# WaterInfo.net
KiCad netlist of a schematic drawn in EasyEDA Pro
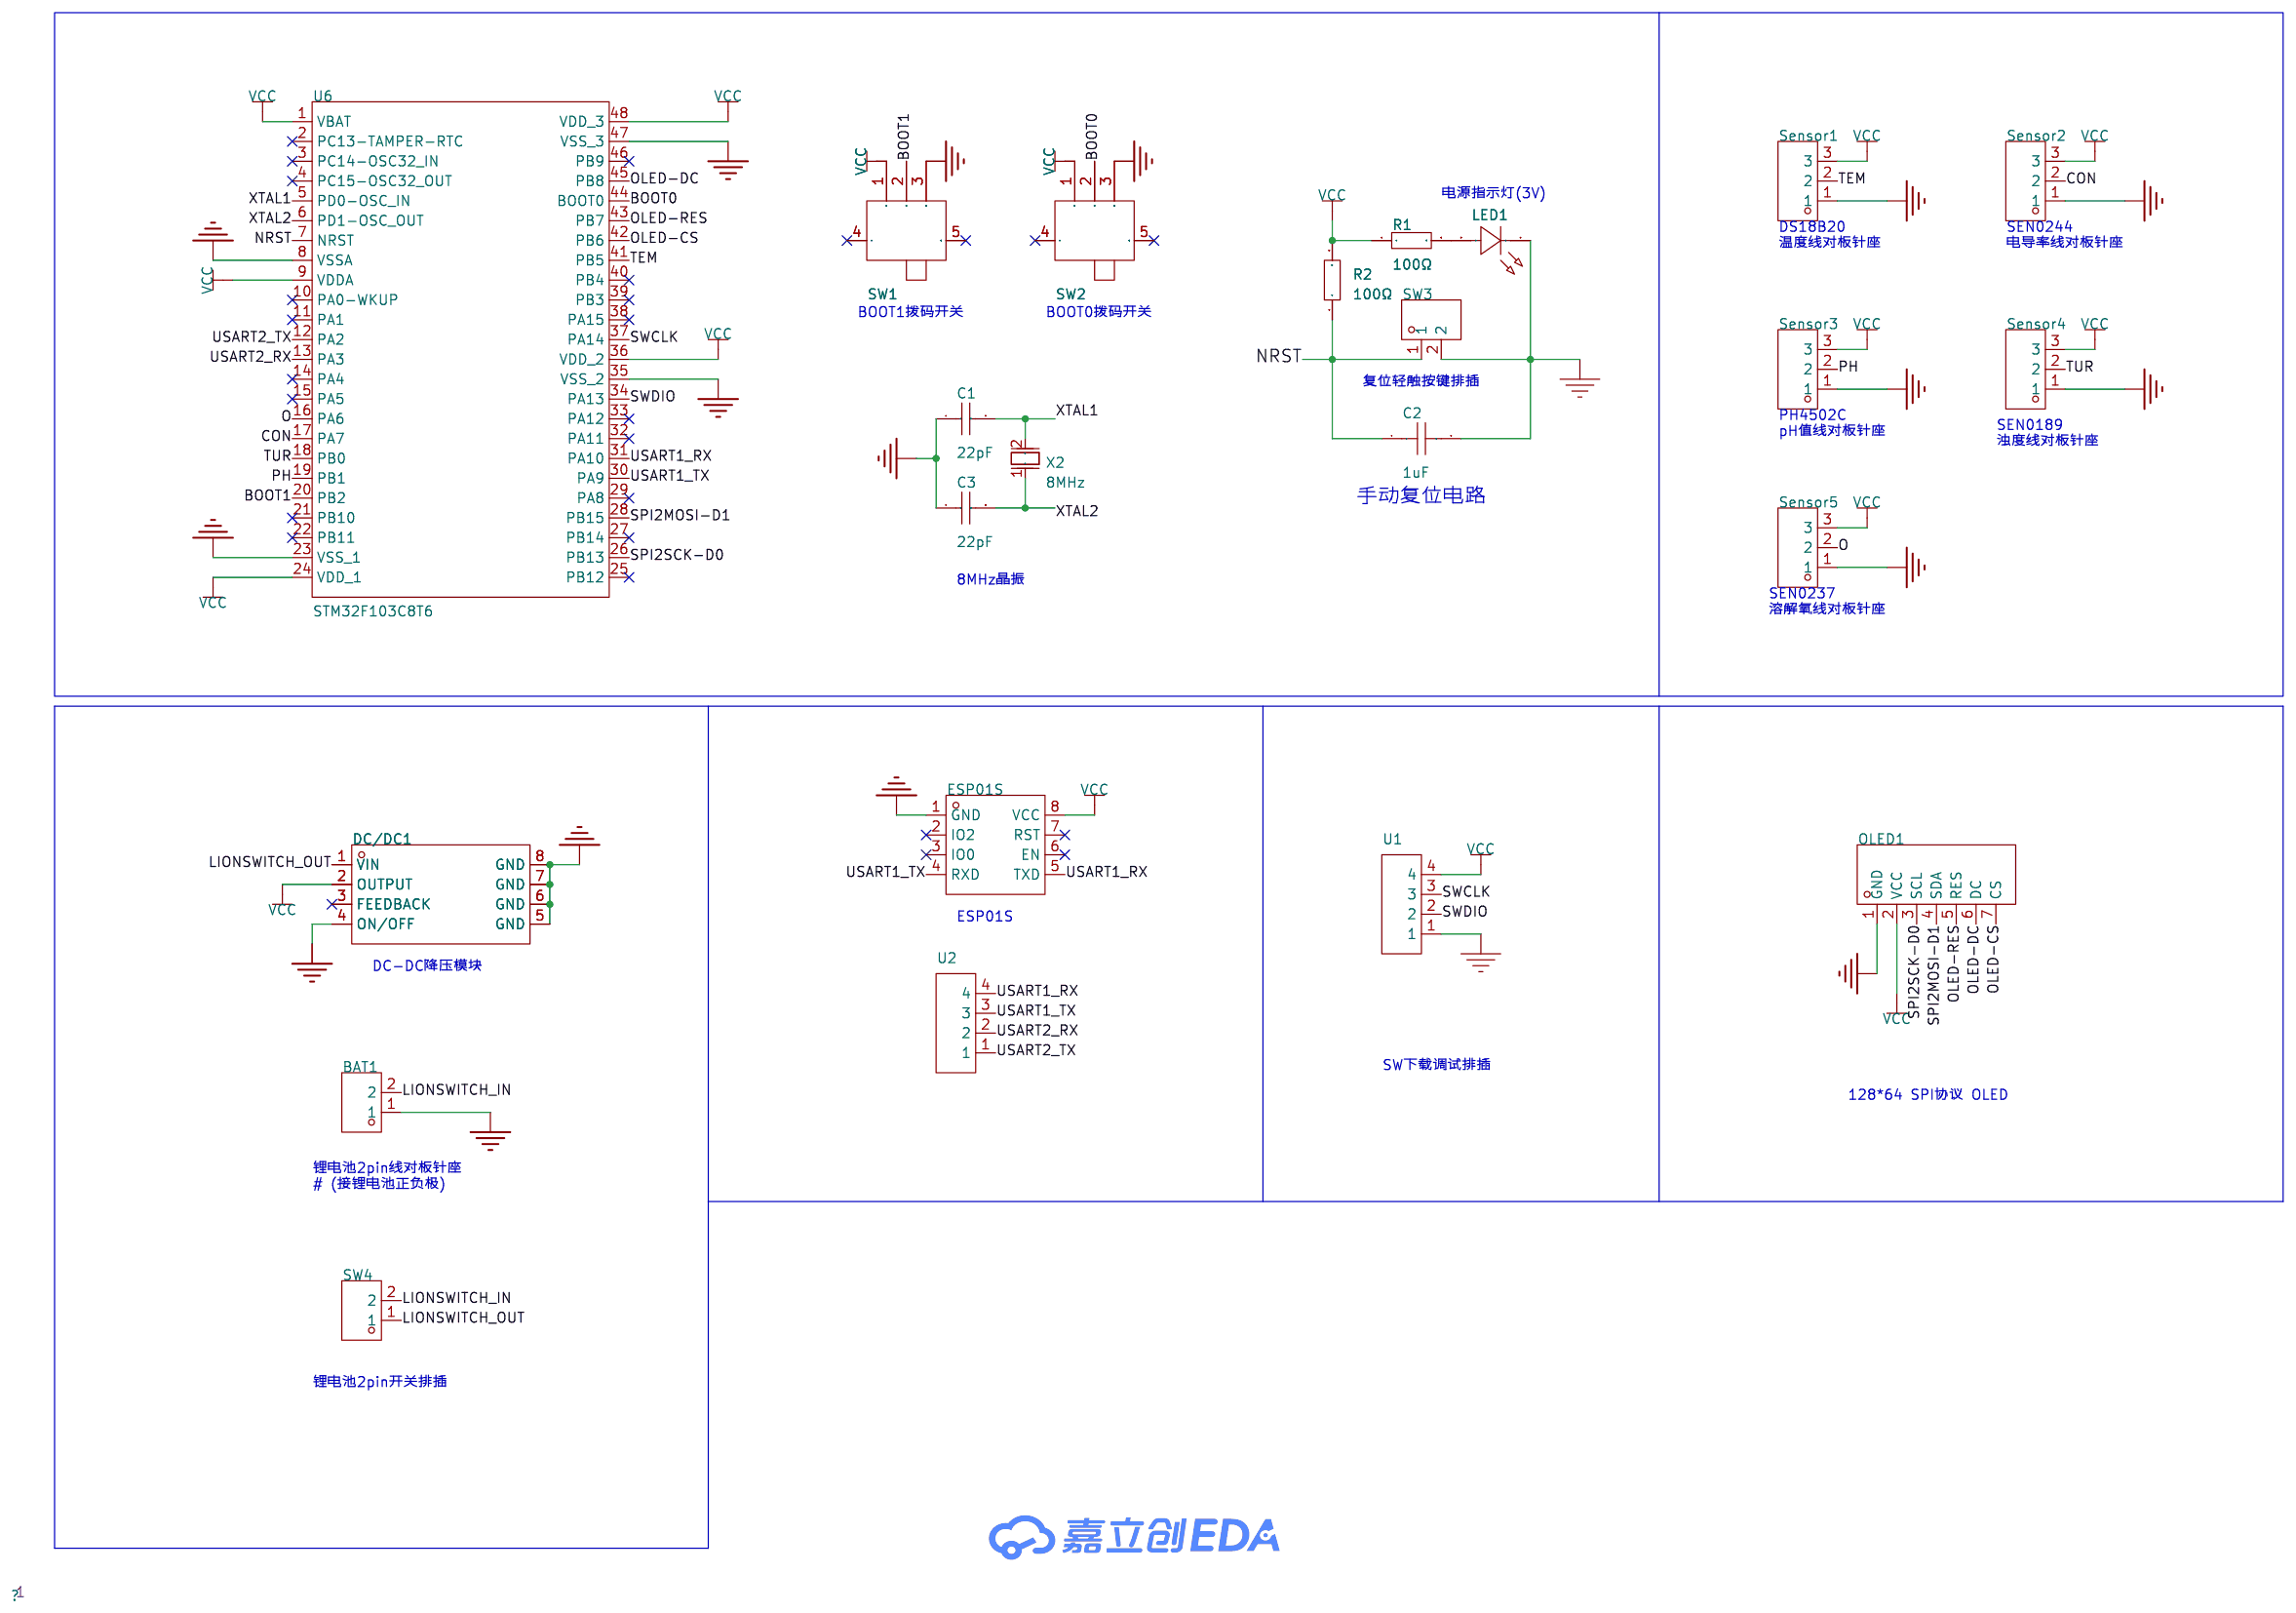
[diagram p0: schematic sheet]

(export (version "E")
  (design (tool "Eeschema 10.0.6"))
  (components
    (comp (ref "BAT1")
      (value "WAFER-PH2.0-2PZZ")
      (footprint "easyedapro:CONN-TH_2P-P2.00_HC-PH-2A-M")
      (fields (field (name "Manufacturer") "XUNPU(讯普)"))
      (libsource (lib "easyedapro") (part "WAFER-PH2.0-2PZZ"))
    )
    (comp (ref "C1")
      (value "22pF")
      (footprint "easyedapro:C0603")
      (description "容值:22pF;精度:±5%;额定电压:50V;材质(温度系数):C0G;")
      (fields
        (field (name "Manufacturer Part") "CL10C220JB8NNNC")
        (field (name "Manufacturer") "SAMSUNG(三星)")
      )
      (libsource (lib "easyedapro") (part "CL10C220JB8NNNC"))
    )
    (comp (ref "C2")
      (value "1uF")
      (footprint "easyedapro:C0603")
      (description "容值:1uF;精度:±10%;额定电压:50V;材质(温度系数):X5R;")
      (fields
        (field (name "Manufacturer Part") "CL10A105KB8NNNC")
        (field (name "Manufacturer") "SAMSUNG(三星)")
      )
      (libsource (lib "easyedapro") (part "CL10A105KB8NNNC"))
    )
    (comp (ref "C3")
      (value "22pF")
      (footprint "easyedapro:C0603")
      (description "容值:22pF;精度:±5%;额定电压:50V;材质(温度系数):C0G;")
      (fields
        (field (name "Manufacturer Part") "CL10C220JB8NNNC")
        (field (name "Manufacturer") "SAMSUNG(三星)")
      )
      (libsource (lib "easyedapro") (part "CL10C220JB8NNNC"))
    )
    (comp (ref "DC/DC1")
      (value "XL1509-3.3")
      (footprint "easyedapro:SOIC-8_L4.9-W3.9-P1.27-LS6.0-BL")
      (description "功能类型:降压型;输出类型:固定;工作电压:4.5V~40V;输出电压:3.3V;输出电流:2A;")
      (fields (field (name "Manufacturer") "UMW(友台半导体)"))
      (libsource (lib "easyedapro") (part "XL1509-3.3"))
    )
    (comp (ref "ESP01S")
      (value "2.4GHz")
      (footprint "easyedapro:WIFIM-TH_8P-L24.7-W14.4-P2.54")
      (description "核心处理器:ESP8266芯片;频率:2.4GHz;天线形式:板载PCB天线;发射功率:16dBm;接收灵敏度:-90dBm;")
      (fields (field (name "Manufacturer Part") "ESP-01S") (field (name "Manufacturer") "Ai-Thinker(安信可)"))
      (libsource (lib "easyedapro") (part "ESP-01S_C503582"))
    )
    (comp (ref "LED1")
      (value "XL-502UGD")
      (footprint "easyedapro:LED-TH_BD5.9-P2.54-RD_GREEN")
      (fields (field (name "Manufacturer") "XINGLIGHT(成兴光)"))
      (libsource (lib "easyedapro") (part "XL-502UGD"))
    )
    (comp (ref "OLED1")
      (value "HS96L01W4S03")
      (footprint "easyedapro:OLED-TH_HS96L01W4S03")
      (fields (field (name "Manufacturer") "HS(汉昇)"))
      (libsource (lib "easyedapro") (part "HS96L01W4S03"))
    )
    (comp (ref "R1")
      (value "100Ω")
      (footprint "easyedapro:R0805")
      (description "电阻类型:薄膜电阻;阻值:100Ω;精度:±0.1%;功率:125mW;最大工作电压:150V;温度系数:±25ppm/°C;")
      (fields (field (name "Manufacturer Part") "RT0805BRD07100RL") (field (name "Manufacturer") "YAGEO(国巨)"))
      (libsource (lib "easyedapro") (part "RT0805BRD07100RL"))
    )
    (comp (ref "R2")
      (value "100Ω")
      (footprint "easyedapro:R0805")
      (description "电阻类型:薄膜电阻;阻值:100Ω;精度:±0.1%;功率:125mW;最大工作电压:150V;温度系数:±25ppm/°C;")
      (fields (field (name "Manufacturer Part") "RT0805BRD07100RL") (field (name "Manufacturer") "YAGEO(国巨)"))
      (libsource (lib "easyedapro") (part "RT0805BRD07100RL"))
    )
    (comp (ref "Sensor1")
      (value "2.54-1*3P")
      (footprint "easyedapro:CONN-TH_C722693")
      (description "插针结构:1x3P;间距:2.5mm;安装方式:直插;参考系列:-;总PIN数:3P;排数:1;每排PIN数:3;行距:-;额定电流:2A;工作温度范围:-25°C~+85°C;")
      (fields (field (name "Manufacturer") "CAX(创都)"))
      (libsource (lib "easyedapro") (part "2.54-1*3P"))
    )
    (comp (ref "Sensor2")
      (value "WAFER-PH2.0-3PZZ")
      (footprint "easyedapro:CONN-TH_PH2.0D-L-3P")
      (fields (field (name "Manufacturer") "XUNPU(讯普)"))
      (libsource (lib "easyedapro") (part "WAFER-PH2.0-3PZZ"))
    )
    (comp (ref "Sensor3")
      (value "2.54-1*3P")
      (footprint "easyedapro:CONN-TH_C722693")
      (description "插针结构:1x3P;间距:2.5mm;安装方式:直插;参考系列:-;总PIN数:3P;排数:1;每排PIN数:3;行距:-;额定电流:2A;工作温度范围:-25°C~+85°C;")
      (fields (field (name "Manufacturer") "CAX(创都)"))
      (libsource (lib "easyedapro") (part "2.54-1*3P"))
    )
    (comp (ref "Sensor4")
      (value "WAFER-PH2.0-3PZZ")
      (footprint "easyedapro:CONN-TH_PH2.0D-L-3P")
      (fields (field (name "Manufacturer") "XUNPU(讯普)"))
      (libsource (lib "easyedapro") (part "WAFER-PH2.0-3PZZ"))
    )
    (comp (ref "Sensor5")
      (value "2.54-1*3P")
      (footprint "easyedapro:CONN-TH_C722693")
      (description "插针结构:1x3P;间距:2.5mm;安装方式:直插;参考系列:-;总PIN数:3P;排数:1;每排PIN数:3;行距:-;额定电流:2A;工作温度范围:-25°C~+85°C;")
      (fields (field (name "Manufacturer") "CAX(创都)"))
      (libsource (lib "easyedapro") (part "2.54-1*3P"))
    )
    (comp (ref "SW1")
      (value "MINI MSK12CO2")
      (footprint "easyedapro:SW-SMD_MSK12CO2")
      (description "电路结构:单刀双掷;安装方式:卧贴;开关颜色:-;额定电流(DC):50mA;额定电压(DC):12V;额定电流(AC):-;额定电压(AC):-;机械寿命:1万次;")
      (fields (field (name "Manufacturer") "SHOU HAN(首韩)"))
      (libsource (lib "easyedapro") (part "MINI MSK12CO2"))
    )
    (comp (ref "SW2")
      (value "MINI MSK12CO2")
      (footprint "easyedapro:SW-SMD_MSK12CO2")
      (description "电路结构:单刀双掷;安装方式:卧贴;开关颜色:-;额定电流(DC):50mA;额定电压(DC):12V;额定电流(AC):-;额定电压(AC):-;机械寿命:1万次;")
      (fields (field (name "Manufacturer") "SHOU HAN(首韩)"))
      (libsource (lib "easyedapro") (part "MINI MSK12CO2"))
    )
    (comp (ref "SW3")
      (value "WAFER-PH2.0-2PZZ")
      (footprint "easyedapro:CONN-TH_2P-P2.00_HC-PH-2A-M")
      (fields (field (name "Manufacturer") "XUNPU(讯普)"))
      (libsource (lib "easyedapro") (part "WAFER-PH2.0-2PZZ"))
    )
    (comp (ref "SW4")
      (value "WAFER-PH2.0-2PZZ")
      (footprint "easyedapro:CONN-TH_2P-P2.00_HC-PH-2A-M")
      (fields (field (name "Manufacturer") "XUNPU(讯普)"))
      (libsource (lib "easyedapro") (part "WAFER-PH2.0-2PZZ"))
    )
    (comp (ref "U1")
      (value "HX PZ2.54-1x4P ZZ")
      (footprint "easyedapro:HDR-TH_4P-P2.54-V-M")
      (fields (field (name "Manufacturer") "hanxia(韩下)"))
      (libsource (lib "easyedapro") (part "HX PZ2.54-1X4P ZZ"))
    )
    (comp (ref "U2")
      (value "HX PZ2.54-1x4P ZZ")
      (footprint "easyedapro:HDR-TH_4P-P2.54-V-M")
      (fields (field (name "Manufacturer") "hanxia(韩下)"))
      (libsource (lib "easyedapro") (part "HX PZ2.54-1X4P ZZ"))
    )
    (comp (ref "U6")
      (value "STM32F103C8T6")
      (footprint "easyedapro:LQFP-48_L7.0-W7.0-P0.50-LS9.0-BL")
      (description "CPU内核:ARM-M3;CPU最大主频:72MHz;应用领域:-;")
      (fields (field (name "Manufacturer") "ST(意法半导体)"))
      (libsource (lib "easyedapro") (part "STM32F103C8T6"))
    )
    (comp (ref "X2")
      (value "8MHz")
      (footprint "easyedapro:OSC-SMD_2P-L3.2-W2.5")
      (description "晶振类型:贴片晶振;频率:8MHz;常温频差:±30ppm;负载电容:12pF;")
      (fields (field (name "Manufacturer Part") "A308000003") (field (name "Manufacturer") "TXC(晶技)"))
      (libsource (lib "easyedapro") (part "A308000003"))
    )
  )
  (nets
    (net (code "1") (name "/BOOT0") (class "Default")
      (node (ref "SW2") (pin "2") (pinfunction "2_2") (pintype "unspecified"))
      (node (ref "U6") (pin "44") (pinfunction "BOOT0_44") (pintype "unspecified"))
    )
    (net (code "2") (name "/BOOT1") (class "Default")
      (node (ref "SW1") (pin "2") (pinfunction "2_2") (pintype "unspecified"))
      (node (ref "U6") (pin "20") (pinfunction "PB2_20") (pintype "unspecified"))
    )
    (net (code "3") (name "/CON") (class "Default")
      (node (ref "Sensor2") (pin "2") (pinfunction "2_2") (pintype "unspecified"))
      (node (ref "U6") (pin "17") (pinfunction "PA7_17") (pintype "unspecified"))
    )
    (net (code "4") (name "/LIONSWITCH_IN") (class "Default")
      (node (ref "BAT1") (pin "2") (pinfunction "2_2") (pintype "unspecified"))
      (node (ref "SW4") (pin "2") (pinfunction "2_2") (pintype "unspecified"))
    )
    (net (code "5") (name "/LIONSWITCH_OUT") (class "Default")
      (node (ref "DC/DC1") (pin "1") (pinfunction "VIN_1") (pintype "unspecified"))
      (node (ref "SW4") (pin "1") (pinfunction "1_1") (pintype "unspecified"))
    )
    (net (code "6") (name "/NRST") (class "Default")
      (node (ref "C2") (pin "1") (pinfunction "1_1") (pintype "unspecified"))
      (node (ref "R2") (pin "1") (pinfunction "1_1") (pintype "input"))
      (node (ref "SW3") (pin "1") (pinfunction "1_1") (pintype "unspecified"))
      (node (ref "U6") (pin "7") (pinfunction "NRST_7") (pintype "unspecified"))
    )
    (net (code "7") (name "/O") (class "Default")
      (node (ref "Sensor5") (pin "2") (pinfunction "2_2") (pintype "unspecified"))
      (node (ref "U6") (pin "16") (pinfunction "PA6_16") (pintype "unspecified"))
    )
    (net (code "8") (name "/OLED-CS") (class "Default")
      (node (ref "OLED1") (pin "7") (pinfunction "CS_7") (pintype "unspecified"))
      (node (ref "U6") (pin "42") (pinfunction "PB6_42") (pintype "unspecified"))
    )
    (net (code "9") (name "/OLED-DC") (class "Default")
      (node (ref "OLED1") (pin "6") (pinfunction "DC_6") (pintype "unspecified"))
      (node (ref "U6") (pin "45") (pinfunction "PB8_45") (pintype "unspecified"))
    )
    (net (code "10") (name "/OLED-RES") (class "Default")
      (node (ref "OLED1") (pin "5") (pinfunction "RES_5") (pintype "unspecified"))
      (node (ref "U6") (pin "43") (pinfunction "PB7_43") (pintype "unspecified"))
    )
    (net (code "11") (name "/PH") (class "Default")
      (node (ref "Sensor3") (pin "2") (pinfunction "2_2") (pintype "unspecified"))
      (node (ref "U6") (pin "19") (pinfunction "PB1_19") (pintype "unspecified"))
    )
    (net (code "12") (name "/SPI2MOSI-D1") (class "Default")
      (node (ref "OLED1") (pin "4") (pinfunction "SDA_4") (pintype "unspecified"))
      (node (ref "U6") (pin "28") (pinfunction "PB15_28") (pintype "unspecified"))
    )
    (net (code "13") (name "/SPI2SCK-D0") (class "Default")
      (node (ref "OLED1") (pin "3") (pinfunction "SCL_3") (pintype "unspecified"))
      (node (ref "U6") (pin "26") (pinfunction "PB13_26") (pintype "unspecified"))
    )
    (net (code "14") (name "/SWCLK") (class "Default")
      (node (ref "U1") (pin "3") (pinfunction "3_3") (pintype "unspecified"))
      (node (ref "U6") (pin "37") (pinfunction "PA14_37") (pintype "unspecified"))
    )
    (net (code "15") (name "/SWDIO") (class "Default")
      (node (ref "U1") (pin "2") (pinfunction "2_2") (pintype "unspecified"))
      (node (ref "U6") (pin "34") (pinfunction "PA13_34") (pintype "unspecified"))
    )
    (net (code "16") (name "/TEM") (class "Default")
      (node (ref "Sensor1") (pin "2") (pinfunction "2_2") (pintype "unspecified"))
      (node (ref "U6") (pin "41") (pinfunction "PB5_41") (pintype "unspecified"))
    )
    (net (code "17") (name "/TUR") (class "Default")
      (node (ref "Sensor4") (pin "2") (pinfunction "2_2") (pintype "unspecified"))
      (node (ref "U6") (pin "18") (pinfunction "PB0_18") (pintype "unspecified"))
    )
    (net (code "18") (name "/USART1_RX") (class "Default")
      (node (ref "ESP01S") (pin "5") (pinfunction "TXD_5") (pintype "unspecified"))
      (node (ref "U2") (pin "4") (pinfunction "4_4") (pintype "unspecified"))
      (node (ref "U6") (pin "31") (pinfunction "PA10_31") (pintype "unspecified"))
    )
    (net (code "19") (name "/USART1_TX") (class "Default")
      (node (ref "ESP01S") (pin "4") (pinfunction "RXD_4") (pintype "unspecified"))
      (node (ref "U2") (pin "3") (pinfunction "3_3") (pintype "unspecified"))
      (node (ref "U6") (pin "30") (pinfunction "PA9_30") (pintype "unspecified"))
    )
    (net (code "20") (name "/USART2_RX") (class "Default")
      (node (ref "U2") (pin "2") (pinfunction "2_2") (pintype "unspecified"))
      (node (ref "U6") (pin "13") (pinfunction "PA3_13") (pintype "unspecified"))
    )
    (net (code "21") (name "/USART2_TX") (class "Default")
      (node (ref "U2") (pin "1") (pinfunction "1_1") (pintype "unspecified"))
      (node (ref "U6") (pin "12") (pinfunction "PA2_12") (pintype "unspecified"))
    )
    (net (code "22") (name "/XTAL1") (class "Default")
      (node (ref "C1") (pin "2") (pinfunction "2_2") (pintype "input"))
      (node (ref "U6") (pin "5") (pinfunction "PD0-OSC_IN_5") (pintype "unspecified"))
      (node (ref "X2") (pin "2") (pinfunction "2_2") (pintype "unspecified"))
    )
    (net (code "23") (name "/XTAL2") (class "Default")
      (node (ref "C3") (pin "2") (pinfunction "2_2") (pintype "input"))
      (node (ref "U6") (pin "6") (pinfunction "PD1-OSC_OUT_6") (pintype "unspecified"))
      (node (ref "X2") (pin "1") (pinfunction "1_1") (pintype "unspecified"))
    )
    (net (code "24") (name "GND") (class "Default")
      (node (ref "BAT1") (pin "1") (pinfunction "1_1") (pintype "unspecified"))
      (node (ref "C1") (pin "1") (pinfunction "1_1") (pintype "input"))
      (node (ref "C2") (pin "2") (pinfunction "2_2") (pintype "unspecified"))
      (node (ref "C3") (pin "1") (pinfunction "1_1") (pintype "input"))
      (node (ref "DC/DC1") (pin "4") (pinfunction "ON/OFF_4") (pintype "unspecified"))
      (node (ref "DC/DC1") (pin "5") (pinfunction "GND_5") (pintype "unspecified"))
      (node (ref "DC/DC1") (pin "6") (pinfunction "GND_6") (pintype "unspecified"))
      (node (ref "DC/DC1") (pin "7") (pinfunction "GND_7") (pintype "unspecified"))
      (node (ref "DC/DC1") (pin "8") (pinfunction "GND_8") (pintype "unspecified"))
      (node (ref "ESP01S") (pin "1") (pinfunction "GND_1") (pintype "unspecified"))
      (node (ref "LED1") (pin "1") (pinfunction "K_1") (pintype "unspecified"))
      (node (ref "OLED1") (pin "1") (pinfunction "GND_1") (pintype "unspecified"))
      (node (ref "SW1") (pin "3") (pinfunction "3_3") (pintype "unspecified"))
      (node (ref "SW2") (pin "3") (pinfunction "3_3") (pintype "unspecified"))
      (node (ref "SW3") (pin "2") (pinfunction "2_2") (pintype "unspecified"))
      (node (ref "Sensor1") (pin "1") (pinfunction "1_1") (pintype "unspecified"))
      (node (ref "Sensor2") (pin "1") (pinfunction "1_1") (pintype "unspecified"))
      (node (ref "Sensor3") (pin "1") (pinfunction "1_1") (pintype "unspecified"))
      (node (ref "Sensor4") (pin "1") (pinfunction "1_1") (pintype "unspecified"))
      (node (ref "Sensor5") (pin "1") (pinfunction "1_1") (pintype "unspecified"))
      (node (ref "U1") (pin "1") (pinfunction "1_1") (pintype "unspecified"))
      (node (ref "U6") (pin "23") (pinfunction "VSS_1_23") (pintype "unspecified"))
      (node (ref "U6") (pin "35") (pinfunction "VSS_2_35") (pintype "unspecified"))
      (node (ref "U6") (pin "47") (pinfunction "VSS_3_47") (pintype "unspecified"))
      (node (ref "U6") (pin "8") (pinfunction "VSSA_8") (pintype "unspecified"))
    )
    (net (code "25") (name "Net-(LED1-A)") (class "Default")
      (node (ref "LED1") (pin "2") (pinfunction "A_2") (pintype "unspecified"))
      (node (ref "R1") (pin "2") (pinfunction "2_2") (pintype "input"))
    )
    (net (code "26") (name "VCC") (class "Default")
      (node (ref "DC/DC1") (pin "2") (pinfunction "OUTPUT_2") (pintype "unspecified"))
      (node (ref "ESP01S") (pin "8") (pinfunction "VCC_8") (pintype "unspecified"))
      (node (ref "OLED1") (pin "2") (pinfunction "VCC_2") (pintype "unspecified"))
      (node (ref "R1") (pin "1") (pinfunction "1_1") (pintype "input"))
      (node (ref "R2") (pin "2") (pinfunction "2_2") (pintype "input"))
      (node (ref "SW1") (pin "1") (pinfunction "1_1") (pintype "unspecified"))
      (node (ref "SW2") (pin "1") (pinfunction "1_1") (pintype "unspecified"))
      (node (ref "Sensor1") (pin "3") (pinfunction "3_3") (pintype "unspecified"))
      (node (ref "Sensor2") (pin "3") (pinfunction "3_3") (pintype "unspecified"))
      (node (ref "Sensor3") (pin "3") (pinfunction "3_3") (pintype "unspecified"))
      (node (ref "Sensor4") (pin "3") (pinfunction "3_3") (pintype "unspecified"))
      (node (ref "Sensor5") (pin "3") (pinfunction "3_3") (pintype "unspecified"))
      (node (ref "U1") (pin "4") (pinfunction "4_4") (pintype "unspecified"))
      (node (ref "U6") (pin "1") (pinfunction "VBAT_1") (pintype "unspecified"))
      (node (ref "U6") (pin "24") (pinfunction "VDD_1_24") (pintype "unspecified"))
      (node (ref "U6") (pin "36") (pinfunction "VDD_2_36") (pintype "unspecified"))
      (node (ref "U6") (pin "48") (pinfunction "VDD_3_48") (pintype "unspecified"))
      (node (ref "U6") (pin "9") (pinfunction "VDDA_9") (pintype "unspecified"))
    )
    (net (code "27") (name "unconnected-(DC/DC1-FEEDBACK-Pad3)") (class "Default")
      (node (ref "DC/DC1") (pin "3") (pinfunction "FEEDBACK_3") (pintype "unspecified+no_connect"))
    )
    (net (code "28") (name "unconnected-(ESP01S-EN-Pad6)") (class "Default")
      (node (ref "ESP01S") (pin "6") (pinfunction "EN_6") (pintype "unspecified+no_connect"))
    )
    (net (code "29") (name "unconnected-(ESP01S-IO0-Pad3)") (class "Default")
      (node (ref "ESP01S") (pin "3") (pinfunction "IO0_3") (pintype "unspecified+no_connect"))
    )
    (net (code "30") (name "unconnected-(ESP01S-IO2-Pad2)") (class "Default")
      (node (ref "ESP01S") (pin "2") (pinfunction "IO2_2") (pintype "unspecified+no_connect"))
    )
    (net (code "31") (name "unconnected-(ESP01S-RST-Pad7)") (class "Default")
      (node (ref "ESP01S") (pin "7") (pinfunction "RST_7") (pintype "unspecified+no_connect"))
    )
    (net (code "32") (name "unconnected-(SW1-Pad4)") (class "Default")
      (node (ref "SW1") (pin "4") (pinfunction "4_4") (pintype "unspecified+no_connect"))
    )
    (net (code "33") (name "unconnected-(SW1-Pad5)") (class "Default")
      (node (ref "SW1") (pin "5") (pinfunction "5_5") (pintype "unspecified+no_connect"))
    )
    (net (code "34") (name "unconnected-(SW2-Pad4)") (class "Default")
      (node (ref "SW2") (pin "4") (pinfunction "4_4") (pintype "unspecified+no_connect"))
    )
    (net (code "35") (name "unconnected-(SW2-Pad5)") (class "Default")
      (node (ref "SW2") (pin "5") (pinfunction "5_5") (pintype "unspecified+no_connect"))
    )
    (net (code "36") (name "unconnected-(U6-PA0-WKUP-Pad10)") (class "Default")
      (node (ref "U6") (pin "10") (pinfunction "PA0-WKUP_10") (pintype "unspecified+no_connect"))
    )
    (net (code "37") (name "unconnected-(U6-PA1-Pad11)") (class "Default")
      (node (ref "U6") (pin "11") (pinfunction "PA1_11") (pintype "unspecified+no_connect"))
    )
    (net (code "38") (name "unconnected-(U6-PA4-Pad14)") (class "Default")
      (node (ref "U6") (pin "14") (pinfunction "PA4_14") (pintype "unspecified+no_connect"))
    )
    (net (code "39") (name "unconnected-(U6-PA5-Pad15)") (class "Default")
      (node (ref "U6") (pin "15") (pinfunction "PA5_15") (pintype "unspecified+no_connect"))
    )
    (net (code "40") (name "unconnected-(U6-PA8-Pad29)") (class "Default")
      (node (ref "U6") (pin "29") (pinfunction "PA8_29") (pintype "unspecified+no_connect"))
    )
    (net (code "41") (name "unconnected-(U6-PA11-Pad32)") (class "Default")
      (node (ref "U6") (pin "32") (pinfunction "PA11_32") (pintype "unspecified+no_connect"))
    )
    (net (code "42") (name "unconnected-(U6-PA12-Pad33)") (class "Default")
      (node (ref "U6") (pin "33") (pinfunction "PA12_33") (pintype "unspecified+no_connect"))
    )
    (net (code "43") (name "unconnected-(U6-PA15-Pad38)") (class "Default")
      (node (ref "U6") (pin "38") (pinfunction "PA15_38") (pintype "unspecified+no_connect"))
    )
    (net (code "44") (name "unconnected-(U6-PB3-Pad39)") (class "Default")
      (node (ref "U6") (pin "39") (pinfunction "PB3_39") (pintype "unspecified+no_connect"))
    )
    (net (code "45") (name "unconnected-(U6-PB4-Pad40)") (class "Default")
      (node (ref "U6") (pin "40") (pinfunction "PB4_40") (pintype "unspecified+no_connect"))
    )
    (net (code "46") (name "unconnected-(U6-PB9-Pad46)") (class "Default")
      (node (ref "U6") (pin "46") (pinfunction "PB9_46") (pintype "unspecified+no_connect"))
    )
    (net (code "47") (name "unconnected-(U6-PB10-Pad21)") (class "Default")
      (node (ref "U6") (pin "21") (pinfunction "PB10_21") (pintype "unspecified+no_connect"))
    )
    (net (code "48") (name "unconnected-(U6-PB11-Pad22)") (class "Default")
      (node (ref "U6") (pin "22") (pinfunction "PB11_22") (pintype "unspecified+no_connect"))
    )
    (net (code "49") (name "unconnected-(U6-PB12-Pad25)") (class "Default")
      (node (ref "U6") (pin "25") (pinfunction "PB12_25") (pintype "unspecified+no_connect"))
    )
    (net (code "50") (name "unconnected-(U6-PB14-Pad27)") (class "Default")
      (node (ref "U6") (pin "27") (pinfunction "PB14_27") (pintype "unspecified+no_connect"))
    )
    (net (code "51") (name "unconnected-(U6-PC13-TAMPER-RTC-Pad2)") (class "Default")
      (node (ref "U6") (pin "2") (pinfunction "PC13-TAMPER-RTC_2") (pintype "unspecified+no_connect"))
    )
    (net (code "52") (name "unconnected-(U6-PC14-OSC32_IN-Pad3)") (class "Default")
      (node (ref "U6") (pin "3") (pinfunction "PC14-OSC32_IN_3") (pintype "unspecified+no_connect"))
    )
    (net (code "53") (name "unconnected-(U6-PC15-OSC32_OUT-Pad4)") (class "Default")
      (node (ref "U6") (pin "4") (pinfunction "PC15-OSC32_OUT_4") (pintype "unspecified+no_connect"))
    )
  )
)
